# firstschematic.net
KiCad netlist of a schematic drawn in EAGLE
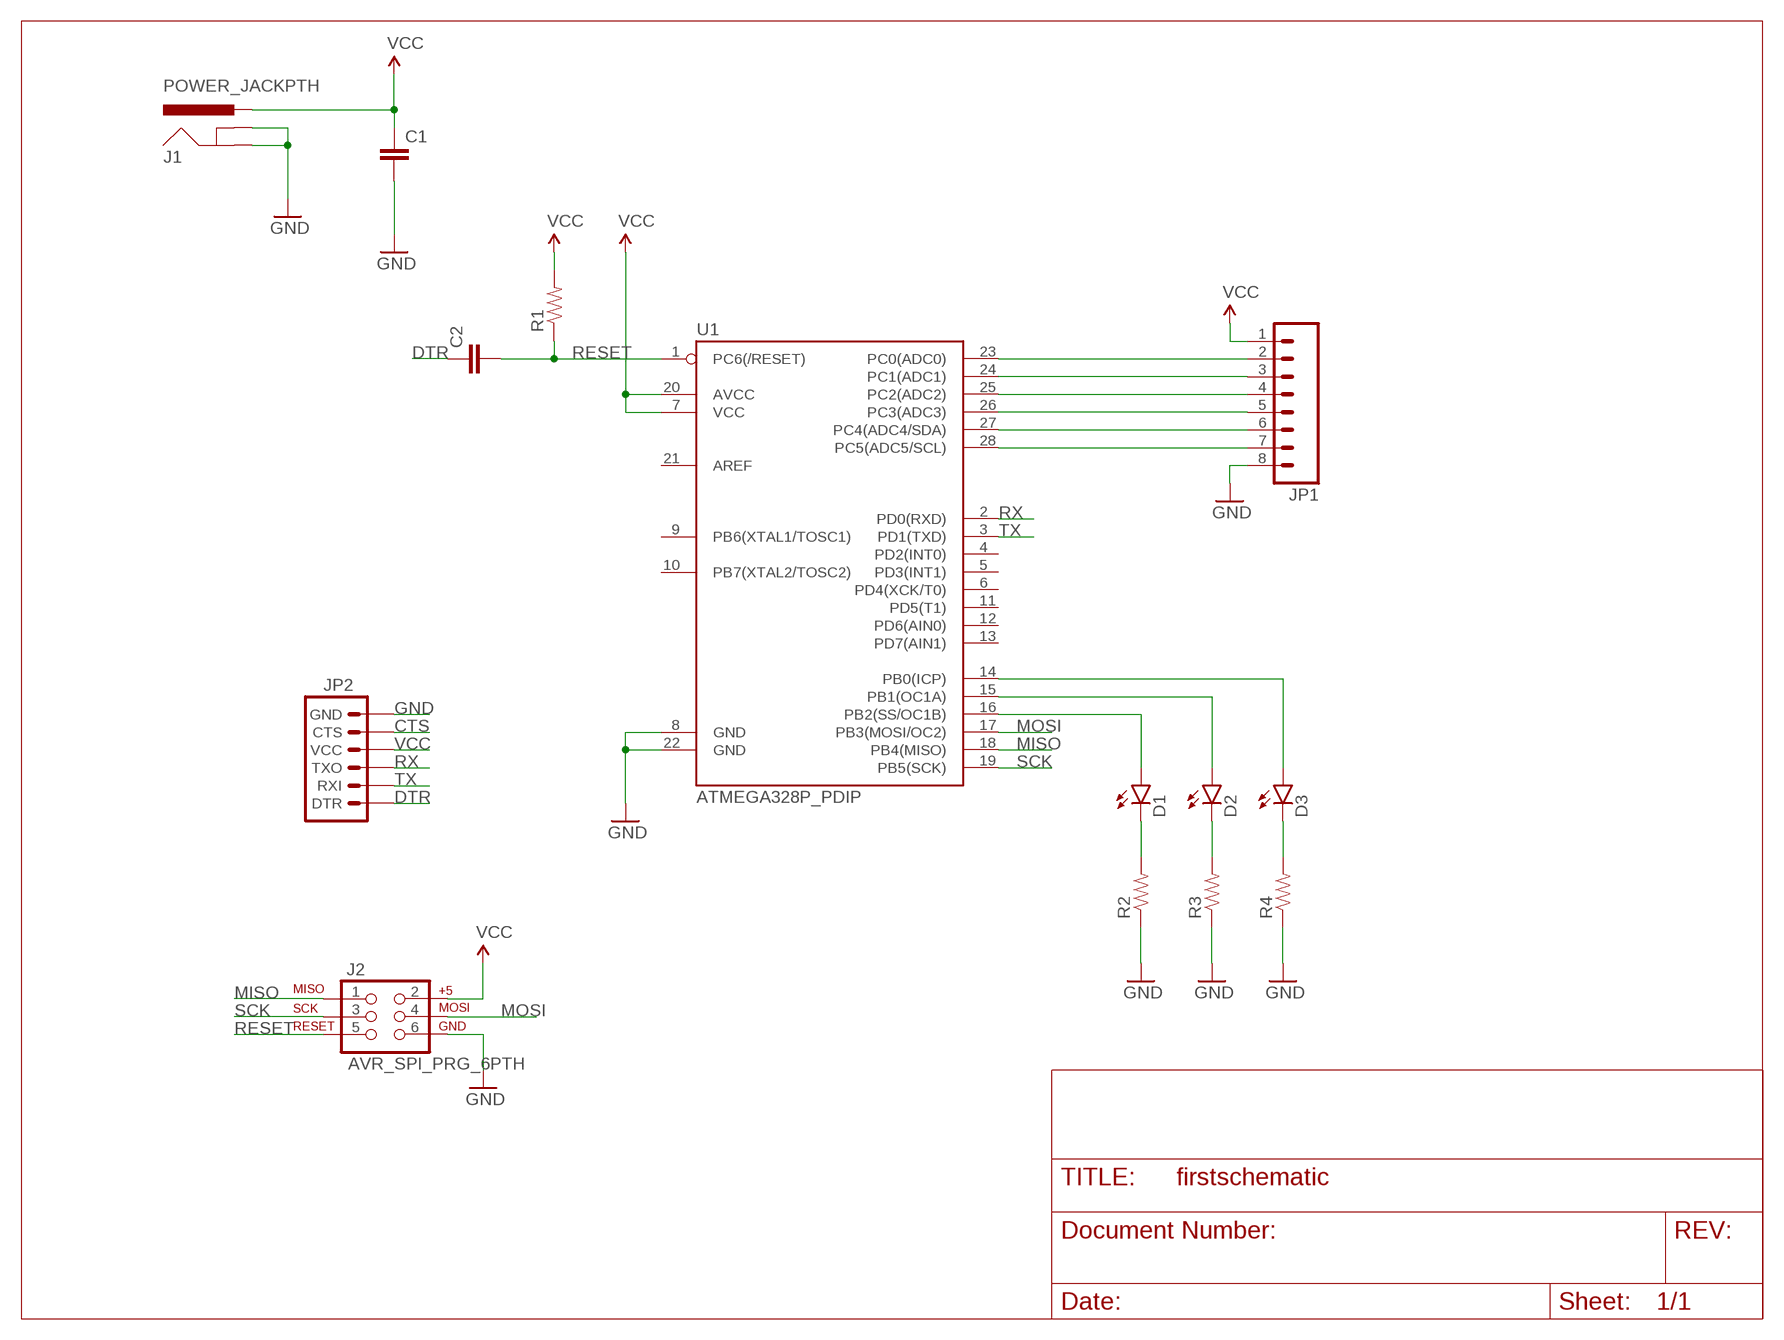
[diagram p0: schematic, sheet 1]

(export (version "E")
  (design (tool "Eeschema 10.0.6"))
  (components
    (comp (ref "C1")
      (value "CAPPTH")
      (footprint "eagle-import:CAP-PTH-SMALL")
      (libsource (lib "eagle-import") (part "CAPPTH"))
    )
    (comp (ref "C2")
      (value "CAPPTH")
      (footprint "eagle-import:CAP-PTH-SMALL")
      (libsource (lib "eagle-import") (part "CAPPTH"))
    )
    (comp (ref "D1")
      (value "LED5MM")
      (footprint "eagle-import:LED5MM")
      (libsource (lib "eagle-import") (part "LED5MM"))
    )
    (comp (ref "D2")
      (value "LED5MM")
      (footprint "eagle-import:LED5MM")
      (libsource (lib "eagle-import") (part "LED5MM"))
    )
    (comp (ref "D3")
      (value "LED5MM")
      (footprint "eagle-import:LED5MM")
      (libsource (lib "eagle-import") (part "LED5MM"))
    )
    (comp (ref "J1")
      (value "POWER_JACKPTH")
      (footprint "eagle-import:POWER_JACK_PTH")
      (libsource (lib "eagle-import") (part "POWER_JACKPTH"))
    )
    (comp (ref "J2")
      (value "AVR_SPI_PRG_6PTH")
      (footprint "eagle-import:2X3")
      (libsource (lib "eagle-import") (part "AVR_SPI_PRG_6PTH"))
    )
    (comp (ref "JP1")
      (value "M08")
      (footprint "eagle-import:1X08_ROUND")
      (libsource (lib "eagle-import") (part "M08"))
    )
    (comp (ref "JP2")
      (value "ARDUINO_SERIAL_PROGRAMPTH")
      (footprint "eagle-import:1X06")
      (libsource (lib "eagle-import") (part "ARDUINO_SERIAL_PROGRAMPTH"))
    )
    (comp (ref "R1")
      (value "RESISTORPTH-1/4W")
      (footprint "eagle-import:AXIAL-0.4")
      (libsource (lib "eagle-import") (part "RESISTORPTH-1/4W"))
    )
    (comp (ref "R2")
      (value "RESISTORPTH-1/4W")
      (footprint "eagle-import:AXIAL-0.4")
      (libsource (lib "eagle-import") (part "RESISTORPTH-1/4W"))
    )
    (comp (ref "R3")
      (value "RESISTORPTH-1/4W")
      (footprint "eagle-import:AXIAL-0.4")
      (libsource (lib "eagle-import") (part "RESISTORPTH-1/4W"))
    )
    (comp (ref "R4")
      (value "RESISTORPTH-1/4W")
      (footprint "eagle-import:AXIAL-0.4")
      (libsource (lib "eagle-import") (part "RESISTORPTH-1/4W"))
    )
    (comp (ref "U1")
      (value "ATMEGA328P_PDIP")
      (footprint "eagle-import:DIL28-3")
      (libsource (lib "eagle-import") (part "ATMEGA328P_PDIP"))
    )
  )
  (nets
    (net (code "1") (name "/CTS") (class "Default")
      (node (ref "JP2") (pin "5") (pinfunction "CTS_5") (pintype "passive"))
    )
    (net (code "2") (name "/DTR") (class "Default")
      (node (ref "C2") (pin "1") (pinfunction "1_1") (pintype "passive"))
      (node (ref "JP2") (pin "1") (pinfunction "DTR_1") (pintype "passive"))
    )
    (net (code "3") (name "/MISO") (class "Default")
      (node (ref "J2") (pin "1") (pinfunction "1_1") (pintype "passive"))
      (node (ref "U1") (pin "18") (pinfunction "PB4(MISO)_18") (pintype "bidirectional"))
    )
    (net (code "4") (name "/MOSI") (class "Default")
      (node (ref "J2") (pin "4") (pinfunction "4_4") (pintype "passive"))
      (node (ref "U1") (pin "17") (pinfunction "PB3(MOSI/OC2)_17") (pintype "bidirectional"))
    )
    (net (code "5") (name "/RESET") (class "Default")
      (node (ref "C2") (pin "2") (pinfunction "2_2") (pintype "passive"))
      (node (ref "J2") (pin "5") (pinfunction "5_5") (pintype "passive"))
      (node (ref "R1") (pin "P$1") (pinfunction "1_P$1") (pintype "passive"))
      (node (ref "U1") (pin "1") (pinfunction "PC6(/RESET)_1") (pintype "bidirectional"))
    )
    (net (code "6") (name "/RX") (class "Default")
      (node (ref "JP2") (pin "3") (pinfunction "TXO_3") (pintype "passive"))
      (node (ref "U1") (pin "2") (pinfunction "PD0(RXD)_2") (pintype "bidirectional"))
    )
    (net (code "7") (name "/SCK") (class "Default")
      (node (ref "J2") (pin "3") (pinfunction "3_3") (pintype "passive"))
      (node (ref "U1") (pin "19") (pinfunction "PB5(SCK)_19") (pintype "bidirectional"))
    )
    (net (code "8") (name "/TX") (class "Default")
      (node (ref "JP2") (pin "2") (pinfunction "RXI_2") (pintype "passive"))
      (node (ref "U1") (pin "3") (pinfunction "PD1(TXD)_3") (pintype "bidirectional"))
    )
    (net (code "9") (name "GND") (class "Default")
      (node (ref "C1") (pin "2") (pinfunction "2_2") (pintype "passive"))
      (node (ref "J1") (pin "GND") (pinfunction "GND_GND") (pintype "bidirectional"))
      (node (ref "J1") (pin "GNDBREAK") (pinfunction "GNDBREAK_GNDBREAK") (pintype "bidirectional"))
      (node (ref "J2") (pin "6") (pinfunction "6_6") (pintype "passive"))
      (node (ref "JP1") (pin "8") (pinfunction "8_8") (pintype "passive"))
      (node (ref "JP2") (pin "6") (pinfunction "GND_6") (pintype "passive"))
      (node (ref "R2") (pin "P$1") (pinfunction "1_P$1") (pintype "passive"))
      (node (ref "R3") (pin "P$1") (pinfunction "1_P$1") (pintype "passive"))
      (node (ref "R4") (pin "P$1") (pinfunction "1_P$1") (pintype "passive"))
      (node (ref "U1") (pin "22") (pinfunction "GND_22") (pintype "bidirectional"))
      (node (ref "U1") (pin "8") (pinfunction "GND_8") (pintype "bidirectional"))
    )
    (net (code "10") (name "Net-(D1-C)") (class "Default")
      (node (ref "D1") (pin "K") (pinfunction "C_K") (pintype "passive"))
      (node (ref "R2") (pin "P$2") (pinfunction "2_P$2") (pintype "passive"))
    )
    (net (code "11") (name "Net-(D2-C)") (class "Default")
      (node (ref "D2") (pin "K") (pinfunction "C_K") (pintype "passive"))
      (node (ref "R3") (pin "P$2") (pinfunction "2_P$2") (pintype "passive"))
    )
    (net (code "12") (name "Net-(D3-C)") (class "Default")
      (node (ref "D3") (pin "K") (pinfunction "C_K") (pintype "passive"))
      (node (ref "R4") (pin "P$2") (pinfunction "2_P$2") (pintype "passive"))
    )
    (net (code "13") (name "Net-(U1-PB0(ICP))") (class "Default")
      (node (ref "D3") (pin "A") (pinfunction "A_A") (pintype "passive"))
      (node (ref "U1") (pin "14") (pinfunction "PB0(ICP)_14") (pintype "bidirectional"))
    )
    (net (code "14") (name "Net-(U1-PB1(OC1A))") (class "Default")
      (node (ref "D2") (pin "A") (pinfunction "A_A") (pintype "passive"))
      (node (ref "U1") (pin "15") (pinfunction "PB1(OC1A)_15") (pintype "bidirectional"))
    )
    (net (code "15") (name "Net-(U1-PB2(SS{slash}OC1B))") (class "Default")
      (node (ref "D1") (pin "A") (pinfunction "A_A") (pintype "passive"))
      (node (ref "U1") (pin "16") (pinfunction "PB2(SS/OC1B)_16") (pintype "bidirectional"))
    )
    (net (code "16") (name "Net-(U1-PC0(ADC0))") (class "Default")
      (node (ref "JP1") (pin "2") (pinfunction "2_2") (pintype "passive"))
      (node (ref "U1") (pin "23") (pinfunction "PC0(ADC0)_23") (pintype "bidirectional"))
    )
    (net (code "17") (name "Net-(U1-PC1(ADC1))") (class "Default")
      (node (ref "JP1") (pin "3") (pinfunction "3_3") (pintype "passive"))
      (node (ref "U1") (pin "24") (pinfunction "PC1(ADC1)_24") (pintype "bidirectional"))
    )
    (net (code "18") (name "Net-(U1-PC2(ADC2))") (class "Default")
      (node (ref "JP1") (pin "4") (pinfunction "4_4") (pintype "passive"))
      (node (ref "U1") (pin "25") (pinfunction "PC2(ADC2)_25") (pintype "bidirectional"))
    )
    (net (code "19") (name "Net-(U1-PC3(ADC3))") (class "Default")
      (node (ref "JP1") (pin "5") (pinfunction "5_5") (pintype "passive"))
      (node (ref "U1") (pin "26") (pinfunction "PC3(ADC3)_26") (pintype "bidirectional"))
    )
    (net (code "20") (name "Net-(U1-PC4(ADC4{slash}SDA))") (class "Default")
      (node (ref "JP1") (pin "6") (pinfunction "6_6") (pintype "passive"))
      (node (ref "U1") (pin "27") (pinfunction "PC4(ADC4/SDA)_27") (pintype "bidirectional"))
    )
    (net (code "21") (name "Net-(U1-PC5(ADC5{slash}SCL))") (class "Default")
      (node (ref "JP1") (pin "7") (pinfunction "7_7") (pintype "passive"))
      (node (ref "U1") (pin "28") (pinfunction "PC5(ADC5/SCL)_28") (pintype "bidirectional"))
    )
    (net (code "22") (name "VCC") (class "Default")
      (node (ref "C1") (pin "1") (pinfunction "1_1") (pintype "passive"))
      (node (ref "J1") (pin "PWR") (pinfunction "PWR_PWR") (pintype "bidirectional"))
      (node (ref "J2") (pin "2") (pinfunction "2_2") (pintype "passive"))
      (node (ref "JP1") (pin "1") (pinfunction "1_1") (pintype "passive"))
      (node (ref "JP2") (pin "4") (pinfunction "VCC_4") (pintype "passive"))
      (node (ref "R1") (pin "P$2") (pinfunction "2_P$2") (pintype "passive"))
      (node (ref "U1") (pin "20") (pinfunction "AVCC_20") (pintype "bidirectional"))
      (node (ref "U1") (pin "7") (pinfunction "VCC_7") (pintype "bidirectional"))
    )
    (net (code "23") (name "unconnected-(U1-AREF-Pad21)") (class "Default")
      (node (ref "U1") (pin "21") (pinfunction "AREF_21") (pintype "bidirectional"))
    )
    (net (code "24") (name "unconnected-(U1-PB6(XTAL1{slash}TOSC1)-Pad9)") (class "Default")
      (node (ref "U1") (pin "9") (pinfunction "PB6(XTAL1/TOSC1)_9") (pintype "bidirectional"))
    )
    (net (code "25") (name "unconnected-(U1-PB7(XTAL2{slash}TOSC2)-Pad10)") (class "Default")
      (node (ref "U1") (pin "10") (pinfunction "PB7(XTAL2/TOSC2)_10") (pintype "bidirectional"))
    )
    (net (code "26") (name "unconnected-(U1-PD2(INT0)-Pad4)") (class "Default")
      (node (ref "U1") (pin "4") (pinfunction "PD2(INT0)_4") (pintype "bidirectional"))
    )
    (net (code "27") (name "unconnected-(U1-PD3(INT1)-Pad5)") (class "Default")
      (node (ref "U1") (pin "5") (pinfunction "PD3(INT1)_5") (pintype "bidirectional"))
    )
    (net (code "28") (name "unconnected-(U1-PD4(XCK{slash}T0)-Pad6)") (class "Default")
      (node (ref "U1") (pin "6") (pinfunction "PD4(XCK/T0)_6") (pintype "bidirectional"))
    )
    (net (code "29") (name "unconnected-(U1-PD5(T1)-Pad11)") (class "Default")
      (node (ref "U1") (pin "11") (pinfunction "PD5(T1)_11") (pintype "bidirectional"))
    )
    (net (code "30") (name "unconnected-(U1-PD6(AIN0)-Pad12)") (class "Default")
      (node (ref "U1") (pin "12") (pinfunction "PD6(AIN0)_12") (pintype "bidirectional"))
    )
    (net (code "31") (name "unconnected-(U1-PD7(AIN1)-Pad13)") (class "Default")
      (node (ref "U1") (pin "13") (pinfunction "PD7(AIN1)_13") (pintype "bidirectional"))
    )
  )
)
